# week_5.net
KiCad netlist of a schematic drawn in EAGLE
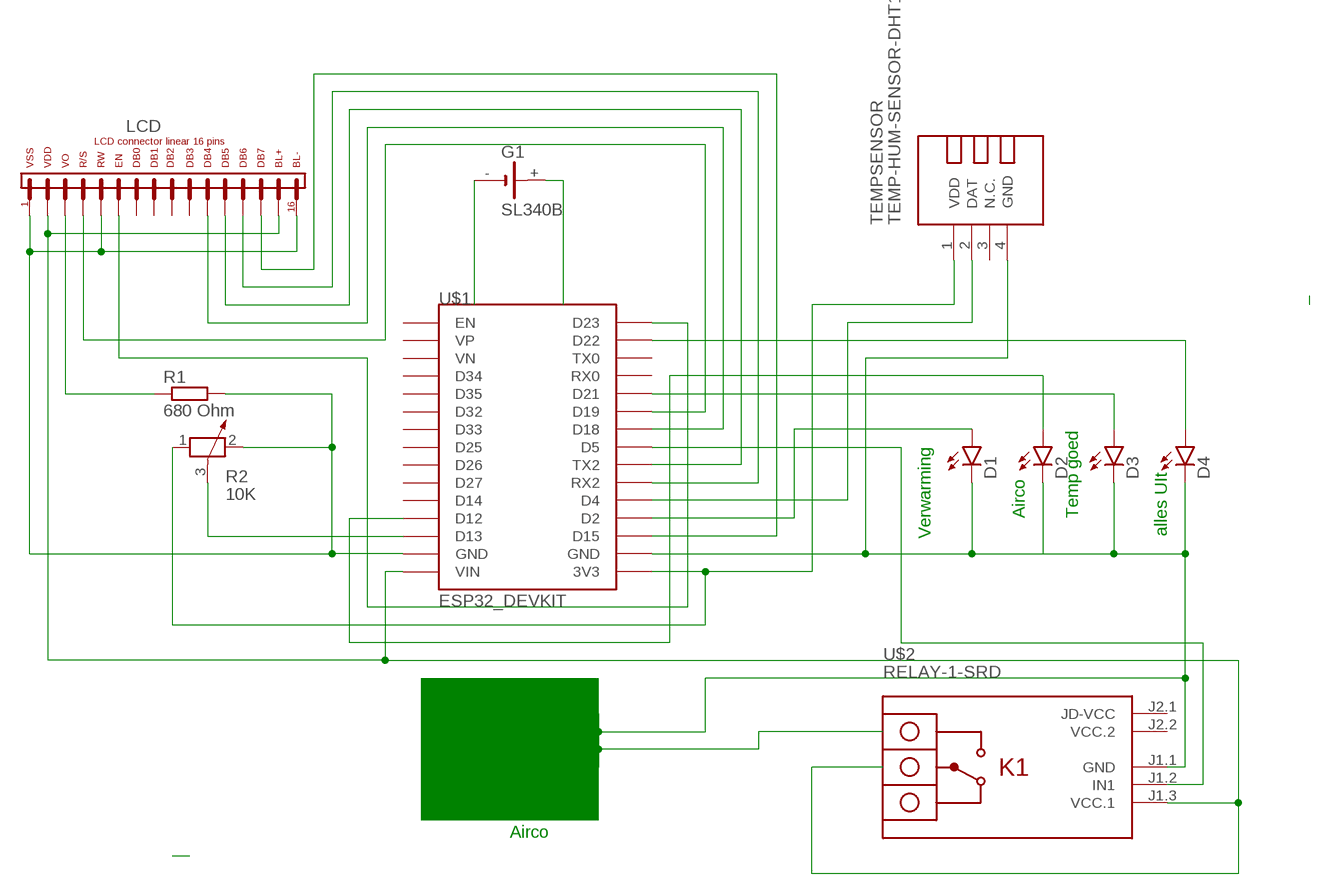
[diagram p0: schematic, sheet 1]

(export (version "E")
  (design (tool "Eeschema 10.0.6"))
  (components
    (comp (ref "D1")
      (value "U57X32")
      (footprint "eagle-import:U57X32")
      (libsource (lib "eagle-import") (part "U57X32"))
    )
    (comp (ref "D2")
      (value "U57X32")
      (footprint "eagle-import:U57X32")
      (libsource (lib "eagle-import") (part "U57X32"))
    )
    (comp (ref "D3")
      (value "U57X32")
      (footprint "eagle-import:U57X32")
      (libsource (lib "eagle-import") (part "U57X32"))
    )
    (comp (ref "D4")
      (value "U57X32")
      (footprint "eagle-import:U57X32")
      (libsource (lib "eagle-import") (part "U57X32"))
    )
    (comp (ref "G1")
      (value "SL340B")
      (footprint "eagle-import:SL-340_B3.6V")
      (libsource (lib "eagle-import") (part "SL340B"))
    )
    (comp (ref "LCD")
      (value "-LCD2X16")
      (footprint "eagle-import:CON8X2LCD")
      (libsource (lib "eagle-import") (part "-LCD2X16"))
    )
    (comp (ref "R1")
      (value "680 Ohm")
      (footprint "eagle-import:0207_10")
      (libsource (lib "eagle-import") (part "R-EU_0207/10"))
    )
    (comp (ref "R2")
      (value "10K")
      (footprint "eagle-import:PT-SPIN")
      (libsource (lib "eagle-import") (part "POTENTIOMETER_PT_SPIN"))
    )
    (comp (ref "TEMPSENSOR")
      (value "TEMP-HUM-SENSOR-DHT11")
      (footprint "eagle-import:TEMP-HUM-SENSOR-DHT11")
      (libsource (lib "eagle-import") (part "TEMP-HUM-SENSOR-DHT11"))
    )
    (comp (ref "U$1")
      (value "ESP32_DEVKIT")
      (footprint "eagle-import:ESP32_DEVKIT")
      (libsource (lib "eagle-import") (part "ESP32_DEVKIT"))
    )
    (comp (ref "U$2")
      (value "RELAY-1-SRD")
      (footprint "eagle-import:RELAY-1-SRD")
      (libsource (lib "eagle-import") (part "RELAY-1-SRD"))
    )
  )
  (nets
    (net (code "1") (name "/VCC.2") (class "Default")
      (node (ref "U$2") (pin "J2.2") (pinfunction "VCC.2_J2.2") (pintype "power_in"))
    )
    (net (code "2") (name "Net-(D1-C)") (class "Default")
      (node (ref "D1") (pin "K") (pinfunction "C_K") (pintype "passive"))
      (node (ref "D2") (pin "K") (pinfunction "C_K") (pintype "passive"))
      (node (ref "D3") (pin "K") (pinfunction "C_K") (pintype "passive"))
      (node (ref "D4") (pin "K") (pinfunction "C_K") (pintype "passive"))
      (node (ref "TEMPSENSOR") (pin "4") (pinfunction "GND_4") (pintype "power_in"))
      (node (ref "U$1") (pin "GND@2") (pinfunction "GND_GND@2") (pintype "bidirectional"))
      (node (ref "U$2") (pin "J1.1") (pinfunction "GND_J1.1") (pintype "power_in"))
    )
    (net (code "3") (name "Net-(D1-PadA)") (class "Default")
      (node (ref "D1") (pin "A") (pinfunction "A_A") (pintype "passive"))
      (node (ref "U$1") (pin "D2") (pinfunction "D2_D2") (pintype "bidirectional"))
    )
    (net (code "4") (name "Net-(D2-PadA)") (class "Default")
      (node (ref "D2") (pin "A") (pinfunction "A_A") (pintype "passive"))
      (node (ref "U$1") (pin "D12") (pinfunction "D12_D12") (pintype "bidirectional"))
    )
    (net (code "5") (name "Net-(D3-PadA)") (class "Default")
      (node (ref "D3") (pin "A") (pinfunction "A_A") (pintype "passive"))
      (node (ref "U$1") (pin "D21") (pinfunction "D21_D21") (pintype "bidirectional"))
    )
    (net (code "6") (name "Net-(D4-PadA)") (class "Default")
      (node (ref "D4") (pin "A") (pinfunction "A_A") (pintype "passive"))
      (node (ref "U$1") (pin "D22") (pinfunction "D22_D22") (pintype "bidirectional"))
    )
    (net (code "7") (name "Net-(LCD-BKL+)") (class "Default")
      (node (ref "LCD") (pin "P$15") (pinfunction "BKL+_P$15") (pintype "passive"))
      (node (ref "LCD") (pin "P$2") (pinfunction "VDD_P$2") (pintype "passive"))
      (node (ref "U$1") (pin "VIN") (pinfunction "VIN_VIN") (pintype "bidirectional"))
      (node (ref "U$2") (pin "J1.3") (pinfunction "VCC.1_J1.3") (pintype "power_in"))
    )
    (net (code "8") (name "Net-(LCD-BKL-)") (class "Default")
      (node (ref "LCD") (pin "P$1") (pinfunction "VSS_P$1") (pintype "passive"))
      (node (ref "LCD") (pin "P$16") (pinfunction "BKL-_P$16") (pintype "passive"))
      (node (ref "LCD") (pin "P$4") (pinfunction "RW_P$4") (pintype "passive"))
      (node (ref "R1") (pin "2") (pinfunction "2_2") (pintype "passive"))
      (node (ref "R2") (pin "2") (pinfunction "2_2") (pintype "passive"))
      (node (ref "U$1") (pin "GND@1") (pinfunction "GND_GND@1") (pintype "bidirectional"))
    )
    (net (code "9") (name "Net-(LCD-DB4)") (class "Default")
      (node (ref "LCD") (pin "P$11") (pinfunction "DB4_P$11") (pintype "passive"))
      (node (ref "U$1") (pin "D18") (pinfunction "D18_D18") (pintype "bidirectional"))
    )
    (net (code "10") (name "Net-(LCD-DB5)") (class "Default")
      (node (ref "LCD") (pin "P$12") (pinfunction "DB5_P$12") (pintype "passive"))
      (node (ref "U$1") (pin "TX2") (pinfunction "TX2_TX2") (pintype "bidirectional"))
    )
    (net (code "11") (name "Net-(LCD-DB6)") (class "Default")
      (node (ref "LCD") (pin "P$13") (pinfunction "DB6_P$13") (pintype "passive"))
      (node (ref "U$1") (pin "RX2") (pinfunction "RX2_RX2") (pintype "bidirectional"))
    )
    (net (code "12") (name "Net-(LCD-DB7)") (class "Default")
      (node (ref "LCD") (pin "P$14") (pinfunction "DB7_P$14") (pintype "passive"))
      (node (ref "U$1") (pin "D15") (pinfunction "D15_D15") (pintype "bidirectional"))
    )
    (net (code "13") (name "Net-(LCD-EN)") (class "Default")
      (node (ref "LCD") (pin "P$6") (pinfunction "EN_P$6") (pintype "passive"))
      (node (ref "U$1") (pin "D23") (pinfunction "D23_D23") (pintype "bidirectional"))
    )
    (net (code "14") (name "Net-(LCD-R{slash}S)") (class "Default")
      (node (ref "LCD") (pin "P$5") (pinfunction "R/S_P$5") (pintype "passive"))
      (node (ref "U$1") (pin "D19") (pinfunction "D19_D19") (pintype "bidirectional"))
    )
    (net (code "15") (name "Net-(LCD-V0)") (class "Default")
      (node (ref "LCD") (pin "P$3") (pinfunction "V0_P$3") (pintype "passive"))
      (node (ref "R1") (pin "1") (pinfunction "1_1") (pintype "passive"))
    )
    (net (code "16") (name "Net-(R2-Pad3)") (class "Default")
      (node (ref "R2") (pin "3") (pinfunction "3_3") (pintype "passive"))
      (node (ref "U$1") (pin "D13") (pinfunction "D13_D13") (pintype "bidirectional"))
    )
    (net (code "17") (name "Net-(TEMPSENSOR-DAT)") (class "Default")
      (node (ref "TEMPSENSOR") (pin "2") (pinfunction "DAT_2") (pintype "bidirectional"))
      (node (ref "U$1") (pin "D4") (pinfunction "D4_D4") (pintype "bidirectional"))
    )
    (net (code "18") (name "Net-(TEMPSENSOR-VDD)") (class "Default")
      (node (ref "R2") (pin "1") (pinfunction "1_1") (pintype "passive"))
      (node (ref "TEMPSENSOR") (pin "1") (pinfunction "VDD_1") (pintype "power_in"))
      (node (ref "U$1") (pin "3V3") (pinfunction "3V3_3V3") (pintype "bidirectional"))
    )
    (net (code "19") (name "Net-(U$2-IN1)") (class "Default")
      (node (ref "U$1") (pin "D5") (pinfunction "D5_D5") (pintype "bidirectional"))
      (node (ref "U$2") (pin "J1.2") (pinfunction "IN1_J1.2") (pintype "bidirectional"))
    )
    (net (code "20") (name "unconnected-(G1-Pad+)") (class "Default")
      (node (ref "G1") (pin "+") (pinfunction "+_+") (pintype "passive"))
    )
    (net (code "21") (name "unconnected-(G1-Pad-)") (class "Default")
      (node (ref "G1") (pin "-") (pinfunction "-_-") (pintype "passive"))
    )
    (net (code "22") (name "unconnected-(LCD-DB0-PadP$7)") (class "Default")
      (node (ref "LCD") (pin "P$7") (pinfunction "DB0_P$7") (pintype "passive"))
    )
    (net (code "23") (name "unconnected-(LCD-DB1-PadP$8)") (class "Default")
      (node (ref "LCD") (pin "P$8") (pinfunction "DB1_P$8") (pintype "passive"))
    )
    (net (code "24") (name "unconnected-(LCD-DB2-PadP$9)") (class "Default")
      (node (ref "LCD") (pin "P$9") (pinfunction "DB2_P$9") (pintype "passive"))
    )
    (net (code "25") (name "unconnected-(LCD-DB3-PadP$10)") (class "Default")
      (node (ref "LCD") (pin "P$10") (pinfunction "DB3_P$10") (pintype "passive"))
    )
    (net (code "26") (name "unconnected-(TEMPSENSOR-N.C.-Pad3)") (class "Default")
      (node (ref "TEMPSENSOR") (pin "3") (pinfunction "N.C._3") (pintype "passive"))
    )
    (net (code "27") (name "unconnected-(U$1-PadD14)") (class "Default")
      (node (ref "U$1") (pin "D14") (pinfunction "D14_D14") (pintype "bidirectional"))
    )
    (net (code "28") (name "unconnected-(U$1-PadD25)") (class "Default")
      (node (ref "U$1") (pin "D25") (pinfunction "D25_D25") (pintype "bidirectional"))
    )
    (net (code "29") (name "unconnected-(U$1-PadD26)") (class "Default")
      (node (ref "U$1") (pin "D26") (pinfunction "D26_D26") (pintype "bidirectional"))
    )
    (net (code "30") (name "unconnected-(U$1-PadD27)") (class "Default")
      (node (ref "U$1") (pin "D27") (pinfunction "D27_D27") (pintype "bidirectional"))
    )
    (net (code "31") (name "unconnected-(U$1-PadD32)") (class "Default")
      (node (ref "U$1") (pin "D32") (pinfunction "D32_D32") (pintype "bidirectional"))
    )
    (net (code "32") (name "unconnected-(U$1-PadD33)") (class "Default")
      (node (ref "U$1") (pin "D33") (pinfunction "D33_D33") (pintype "bidirectional"))
    )
    (net (code "33") (name "unconnected-(U$1-PadD34)") (class "Default")
      (node (ref "U$1") (pin "D34") (pinfunction "D34_D34") (pintype "bidirectional"))
    )
    (net (code "34") (name "unconnected-(U$1-PadD35)") (class "Default")
      (node (ref "U$1") (pin "D35") (pinfunction "D35_D35") (pintype "bidirectional"))
    )
    (net (code "35") (name "unconnected-(U$1-PadEN)") (class "Default")
      (node (ref "U$1") (pin "EN") (pinfunction "EN_EN") (pintype "bidirectional"))
    )
    (net (code "36") (name "unconnected-(U$1-PadRX0)") (class "Default")
      (node (ref "U$1") (pin "RX0") (pinfunction "RX0_RX0") (pintype "bidirectional"))
    )
    (net (code "37") (name "unconnected-(U$1-PadTX0)") (class "Default")
      (node (ref "U$1") (pin "TX0") (pinfunction "TX0_TX0") (pintype "bidirectional"))
    )
    (net (code "38") (name "unconnected-(U$1-PadVN)") (class "Default")
      (node (ref "U$1") (pin "VN") (pinfunction "VN_VN") (pintype "bidirectional"))
    )
    (net (code "39") (name "unconnected-(U$1-PadVP)") (class "Default")
      (node (ref "U$1") (pin "VP") (pinfunction "VP_VP") (pintype "bidirectional"))
    )
    (net (code "40") (name "unconnected-(U$2-JD-VCC-PadJ2.1)") (class "Default")
      (node (ref "U$2") (pin "J2.1") (pinfunction "JD-VCC_J2.1") (pintype "bidirectional"))
    )
  )
)
